# microController.net
KiCad netlist of a schematic drawn in Altium Designer
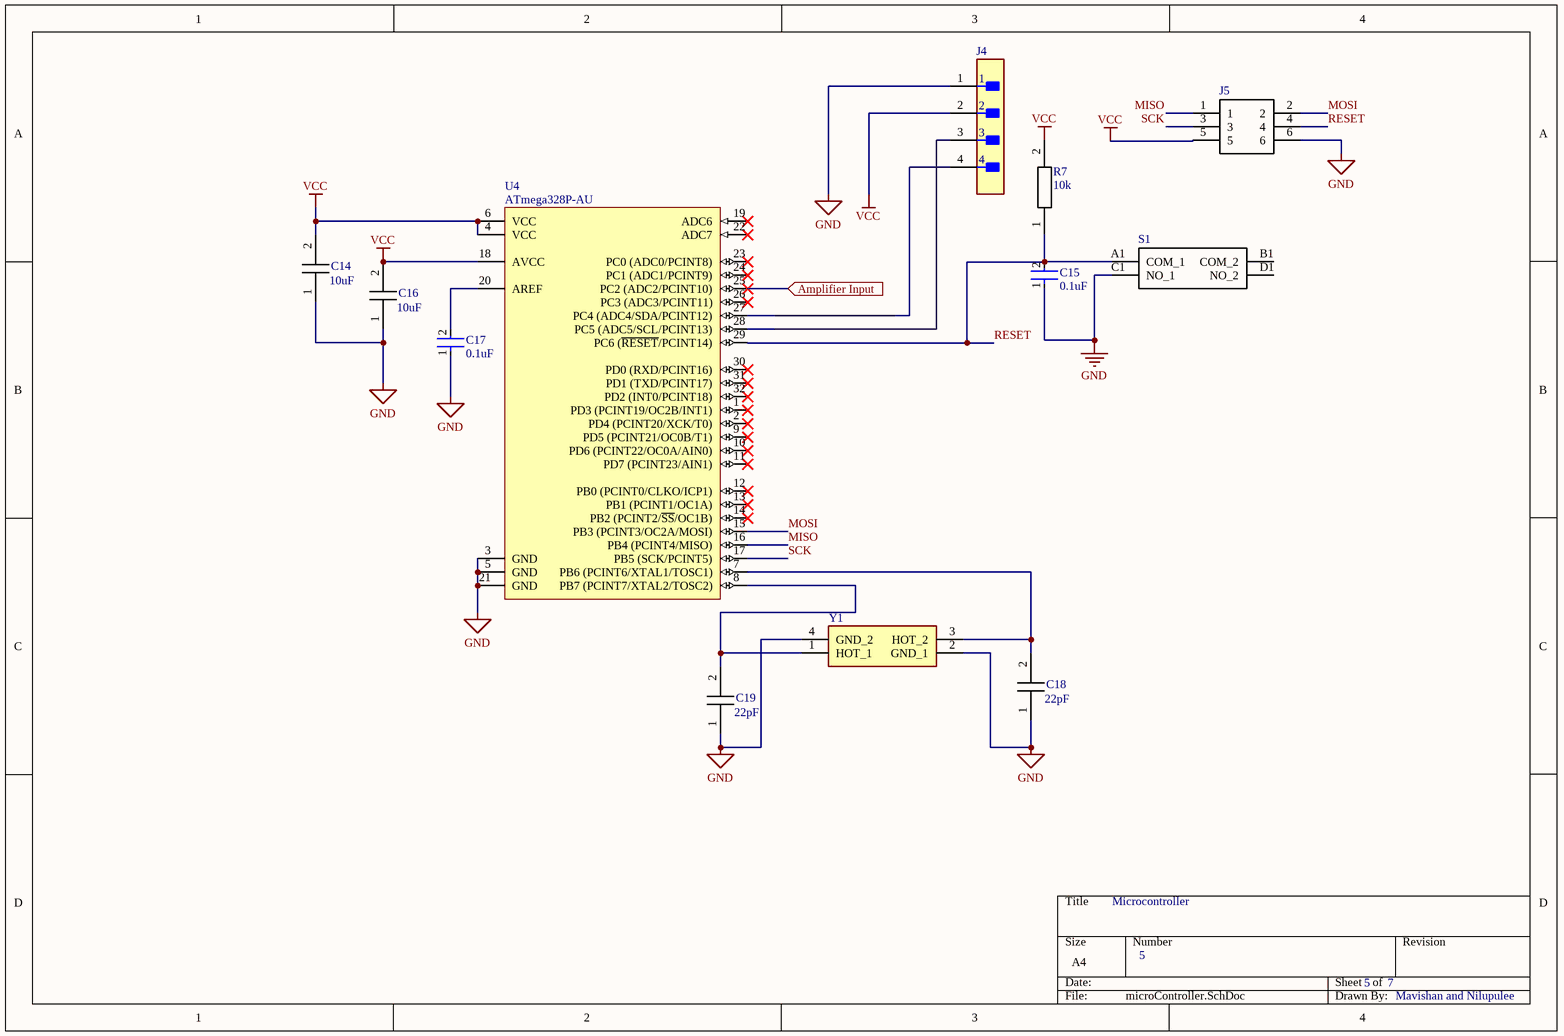
[diagram p0: microController.SchDoc]

(export (version "E")
  (design (tool "Eeschema 10.0.6"))
  (components
    (comp (ref "C14")
      (value "CGA5L1X7R1C106K160AC")
      (footprint "SamacSys:CAPC3216X190N")
      (description "Capacitor")
      (fields (field (name "MOUSER PART NUMBER") "810-CGA5L1X7R1C106KC") (field (name "PARAMETER 2") "10uF"))
      (libsource (lib "SamacSys") (part "CGA5L1X7R1C106K160AC"))
    )
    (comp (ref "C15")
      (value "0.1uF")
      (footprint "FP-C1206C-EB-MFG")
      (description "CAP CER 0.1UF 25V C0G/NP0 1206")
      (fields
        (field (name "MANUFACTURER") "KEMET")
        (field (name "MANUFACTURER PART NUMBER") "C1206C104F3GACTU")
      )
      (libsource (lib "Altium Content Vault") (part "b4654b650e69147ec39a6b967a45e02"))
    )
    (comp (ref "C16")
      (value "CGA5L1X7R1C106K160AC")
      (footprint "SamacSys:CAPC3216X190N")
      (description "Capacitor")
      (fields (field (name "MOUSER PART NUMBER") "810-CGA5L1X7R1C106KC") (field (name "PARAMETER 1") "10uF"))
      (libsource (lib "SamacSys") (part "CGA5L1X7R1C106K160AC"))
    )
    (comp (ref "C17")
      (value "0.1uF")
      (footprint "FP-C1206C-EB-MFG")
      (description "CAP CER 0.1UF 25V C0G/NP0 1206")
      (fields
        (field (name "MANUFACTURER") "KEMET")
        (field (name "MANUFACTURER PART NUMBER") "C1206C104F3GACTU")
      )
      (libsource (lib "Altium Content Vault") (part "b4654b650e69147ec39a6b967a45e02"))
    )
    (comp (ref "C18")
      (value "12063A220JAT2A")
      (footprint "SamacSys:CAPC3216X94N")
      (description "Capacitor")
      (fields (field (name "MOUSER PART NUMBER") "581-12063A220JAT2A") (field (name "PARAMETER 1") "22pF"))
      (libsource (lib "SamacSys") (part "12063A220JAT2A"))
    )
    (comp (ref "C19")
      (value "12063A220JAT2A")
      (footprint "SamacSys:CAPC3216X94N")
      (description "Capacitor")
      (fields (field (name "MOUSER PART NUMBER") "581-12063A220JAT2A") (field (name "PARAMETER 1") "22pF"))
      (libsource (lib "SamacSys") (part "12063A220JAT2A"))
    )
    (comp (ref "J4")
      (value "B4B-XH-A(LF)(SN)")
      (footprint "FP-B4B-XH-A_LF_SN-MFG")
      (description "CONN HEADER VERT 4POS 2.5MM")
      (libsource (lib "Altium Content Vault") (part "299a8cea1bdcbc3624fe62c390fa72c"))
    )
    (comp (ref "J5")
      (value "87914-0606")
      (footprint "SamacSys:HDRV6W69P254_2X3_762X498X859P")
      (description "Connector")
      (fields (field (name "MOUSER PART NUMBER") "538-87914-0606"))
      (libsource (lib "*") (part "87914-0606"))
    )
    (comp (ref "R7")
      (value "ERA-8AEB103V")
      (footprint "SamacSys:RESC3216X70N")
      (description "Resistor")
      (fields (field (name "MOUSER PART NUMBER") "667-ERA-8AEB103V") (field (name "PARAMETER 1") "10k"))
      (libsource (lib "SamacSys") (part "ERA-8AEB103V"))
    )
    (comp (ref "S1")
      (value "TS-1187A-B-A-B")
      (footprint "SamacSys:TS1187ABAB")
      (description "Switch")
      (libsource (lib "*") (part "TS-1187A-B-A-B"))
    )
    (comp (ref "U4")
      (value "ATmega328P-AU")
      (footprint "32A_M")
      (libsource (lib "Altium Content Vault") (part "MC-8B-ATM48-SQ32"))
    )
    (comp (ref "Y1")
      (value "CX3225SA40000D0PTWCC")
      (footprint "SamacSys:CX3225SA40000D0PTWCC")
      (description "Crystal or Oscillator")
      (fields (field (name "MOUSER PART NUMBER") "581-CX3225SA40D0PTWC"))
      (libsource (lib "*") (part "CX3225SA40000D0PTWCC"))
    )
  )
  (nets
    (net (code "1") (name "/Amplifier Input") (class "Default")
      (node (ref "U4") (pin "25") (pinfunction "PC2_(ADC2/PCINT10)_25") (pintype "bidirectional+no_connect"))
    )
    (net (code "2") (name "/MISO") (class "Default")
      (node (ref "J5") (pin "1") (pinfunction "1_1") (pintype "passive"))
      (node (ref "U4") (pin "16") (pinfunction "PB4_(PCINT4/MISO)_16") (pintype "bidirectional"))
    )
    (net (code "3") (name "/MOSI") (class "Default")
      (node (ref "J5") (pin "2") (pinfunction "2_2") (pintype "passive"))
      (node (ref "U4") (pin "15") (pinfunction "PB3_(PCINT3/OC2A/MOSI)_15") (pintype "bidirectional"))
    )
    (net (code "4") (name "/RESET") (class "Default")
      (node (ref "C15") (pin "2") (pinfunction "2_2") (pintype "passive"))
      (node (ref "J5") (pin "4") (pinfunction "4_4") (pintype "passive"))
      (node (ref "R7") (pin "1") (pinfunction "1_1") (pintype "passive"))
      (node (ref "S1") (pin "A1") (pinfunction "COM_1_A1") (pintype "passive"))
      (node (ref "U4") (pin "29") (pinfunction "PC6_(~{RESET}/PCINT14)_29") (pintype "bidirectional"))
    )
    (net (code "5") (name "/SCK") (class "Default")
      (node (ref "J5") (pin "3") (pinfunction "3_3") (pintype "passive"))
      (node (ref "U4") (pin "17") (pinfunction "PB5_(SCK/PCINT5)_17") (pintype "bidirectional"))
    )
    (net (code "6") (name "GND") (class "Default")
      (node (ref "C14") (pin "1") (pinfunction "1_1") (pintype "passive"))
      (node (ref "C15") (pin "1") (pinfunction "1_1") (pintype "passive"))
      (node (ref "C16") (pin "1") (pinfunction "1_1") (pintype "passive"))
      (node (ref "C17") (pin "1") (pinfunction "1_1") (pintype "passive"))
      (node (ref "C18") (pin "1") (pinfunction "C1_1") (pintype "passive"))
      (node (ref "C19") (pin "1") (pinfunction "C1_1") (pintype "passive"))
      (node (ref "J4") (pin "1") (pinfunction "1_1") (pintype "passive"))
      (node (ref "J5") (pin "6") (pinfunction "6_6") (pintype "passive"))
      (node (ref "S1") (pin "C1") (pinfunction "NO_1_C1") (pintype "passive"))
      (node (ref "U4") (pin "21") (pinfunction "GND_21") (pintype "power_in"))
      (node (ref "U4") (pin "3") (pinfunction "GND_3") (pintype "power_in"))
      (node (ref "U4") (pin "5") (pinfunction "GND_5") (pintype "power_in"))
      (node (ref "Y1") (pin "2") (pinfunction "GND_1_2") (pintype "passive"))
      (node (ref "Y1") (pin "4") (pinfunction "GND_2_4") (pintype "passive"))
    )
    (net (code "7") (name "Net-(C18-C2)") (class "Default")
      (node (ref "C18") (pin "2") (pinfunction "C2_2") (pintype "passive"))
      (node (ref "U4") (pin "7") (pinfunction "PB6_(PCINT6/XTAL1/TOSC1)_7") (pintype "bidirectional"))
      (node (ref "Y1") (pin "3") (pinfunction "HOT_2_3") (pintype "passive"))
    )
    (net (code "8") (name "Net-(C19-C2)") (class "Default")
      (node (ref "C19") (pin "2") (pinfunction "C2_2") (pintype "passive"))
      (node (ref "U4") (pin "8") (pinfunction "PB7_(PCINT7/XTAL2/TOSC2)_8") (pintype "bidirectional"))
      (node (ref "Y1") (pin "1") (pinfunction "HOT_1_1") (pintype "passive"))
    )
    (net (code "9") (name "Net-(U4-AREF)") (class "Default")
      (node (ref "C17") (pin "2") (pinfunction "2_2") (pintype "passive"))
      (node (ref "U4") (pin "20") (pinfunction "AREF_20") (pintype "passive"))
    )
    (net (code "10") (name "Net-(U4-PC4_(ADC4{slash}SDA{slash}PCINT12))") (class "Default")
      (node (ref "J4") (pin "4") (pinfunction "4_4") (pintype "passive"))
      (node (ref "U4") (pin "27") (pinfunction "PC4_(ADC4/SDA/PCINT12)_27") (pintype "bidirectional"))
    )
    (net (code "11") (name "Net-(U4-PC5_(ADC5{slash}SCL{slash}PCINT13))") (class "Default")
      (node (ref "J4") (pin "3") (pinfunction "3_3") (pintype "passive"))
      (node (ref "U4") (pin "28") (pinfunction "PC5_(ADC5/SCL/PCINT13)_28") (pintype "bidirectional"))
    )
    (net (code "12") (name "VCC") (class "Default")
      (node (ref "C14") (pin "2") (pinfunction "2_2") (pintype "passive"))
      (node (ref "C16") (pin "2") (pinfunction "2_2") (pintype "passive"))
      (node (ref "J4") (pin "2") (pinfunction "2_2") (pintype "passive"))
      (node (ref "J5") (pin "5") (pinfunction "5_5") (pintype "passive"))
      (node (ref "R7") (pin "2") (pinfunction "2_2") (pintype "passive"))
      (node (ref "U4") (pin "18") (pinfunction "AVCC_18") (pintype "power_in"))
      (node (ref "U4") (pin "4") (pinfunction "VCC_4") (pintype "power_in"))
      (node (ref "U4") (pin "6") (pinfunction "VCC_6") (pintype "power_in"))
    )
    (net (code "13") (name "unconnected-(S1-COM_2-PadB1)") (class "Default")
      (node (ref "S1") (pin "B1") (pinfunction "COM_2_B1") (pintype "passive"))
    )
    (net (code "14") (name "unconnected-(S1-NO_2-PadD1)") (class "Default")
      (node (ref "S1") (pin "D1") (pinfunction "NO_2_D1") (pintype "passive"))
    )
    (net (code "15") (name "unconnected-(U4-ADC6-Pad19)") (class "Default")
      (node (ref "U4") (pin "19") (pinfunction "ADC6_19") (pintype "input+no_connect"))
    )
    (net (code "16") (name "unconnected-(U4-ADC7-Pad22)") (class "Default")
      (node (ref "U4") (pin "22") (pinfunction "ADC7_22") (pintype "input+no_connect"))
    )
    (net (code "17") (name "unconnected-(U4-PB0_(PCINT0{slash}CLKO{slash}ICP1)-Pad12)") (class "Default")
      (node (ref "U4") (pin "12") (pinfunction "PB0_(PCINT0/CLKO/ICP1)_12") (pintype "bidirectional+no_connect"))
    )
    (net (code "18") (name "unconnected-(U4-PB1_(PCINT1{slash}OC1A)-Pad13)") (class "Default")
      (node (ref "U4") (pin "13") (pinfunction "PB1_(PCINT1/OC1A)_13") (pintype "bidirectional+no_connect"))
    )
    (net (code "19") (name "unconnected-(U4-PB2_(PCINT2{slash}~{SS}{slash}OC1B)-Pad14)") (class "Default")
      (node (ref "U4") (pin "14") (pinfunction "PB2_(PCINT2/~{SS}/OC1B)_14") (pintype "bidirectional+no_connect"))
    )
    (net (code "20") (name "unconnected-(U4-PC0_(ADC0{slash}PCINT8)-Pad23)") (class "Default")
      (node (ref "U4") (pin "23") (pinfunction "PC0_(ADC0/PCINT8)_23") (pintype "bidirectional+no_connect"))
    )
    (net (code "21") (name "unconnected-(U4-PC1_(ADC1{slash}PCINT9)-Pad24)") (class "Default")
      (node (ref "U4") (pin "24") (pinfunction "PC1_(ADC1/PCINT9)_24") (pintype "bidirectional+no_connect"))
    )
    (net (code "22") (name "unconnected-(U4-PC3_(ADC3{slash}PCINT11)-Pad26)") (class "Default")
      (node (ref "U4") (pin "26") (pinfunction "PC3_(ADC3/PCINT11)_26") (pintype "bidirectional+no_connect"))
    )
    (net (code "23") (name "unconnected-(U4-PD0_(RXD{slash}PCINT16)-Pad30)") (class "Default")
      (node (ref "U4") (pin "30") (pinfunction "PD0_(RXD/PCINT16)_30") (pintype "bidirectional+no_connect"))
    )
    (net (code "24") (name "unconnected-(U4-PD1_(TXD{slash}PCINT17)-Pad31)") (class "Default")
      (node (ref "U4") (pin "31") (pinfunction "PD1_(TXD/PCINT17)_31") (pintype "bidirectional+no_connect"))
    )
    (net (code "25") (name "unconnected-(U4-PD2_(INT0{slash}PCINT18)-Pad32)") (class "Default")
      (node (ref "U4") (pin "32") (pinfunction "PD2_(INT0/PCINT18)_32") (pintype "bidirectional+no_connect"))
    )
    (net (code "26") (name "unconnected-(U4-PD3_(PCINT19{slash}OC2B{slash}INT1)-Pad1)") (class "Default")
      (node (ref "U4") (pin "1") (pinfunction "PD3_(PCINT19/OC2B/INT1)_1") (pintype "bidirectional+no_connect"))
    )
    (net (code "27") (name "unconnected-(U4-PD4_(PCINT20{slash}XCK{slash}T0)-Pad2)") (class "Default")
      (node (ref "U4") (pin "2") (pinfunction "PD4_(PCINT20/XCK/T0)_2") (pintype "bidirectional+no_connect"))
    )
    (net (code "28") (name "unconnected-(U4-PD5_(PCINT21{slash}OC0B{slash}T1)-Pad9)") (class "Default")
      (node (ref "U4") (pin "9") (pinfunction "PD5_(PCINT21/OC0B/T1)_9") (pintype "bidirectional+no_connect"))
    )
    (net (code "29") (name "unconnected-(U4-PD6_(PCINT22{slash}OC0A{slash}AIN0)-Pad10)") (class "Default")
      (node (ref "U4") (pin "10") (pinfunction "PD6_(PCINT22/OC0A/AIN0)_10") (pintype "bidirectional+no_connect"))
    )
    (net (code "30") (name "unconnected-(U4-PD7_(PCINT23{slash}AIN1)-Pad11)") (class "Default")
      (node (ref "U4") (pin "11") (pinfunction "PD7_(PCINT23/AIN1)_11") (pintype "bidirectional+no_connect"))
    )
  )
)
